# SERIAL_INTERFACES.net
KiCad netlist of a schematic drawn in Altium Designer
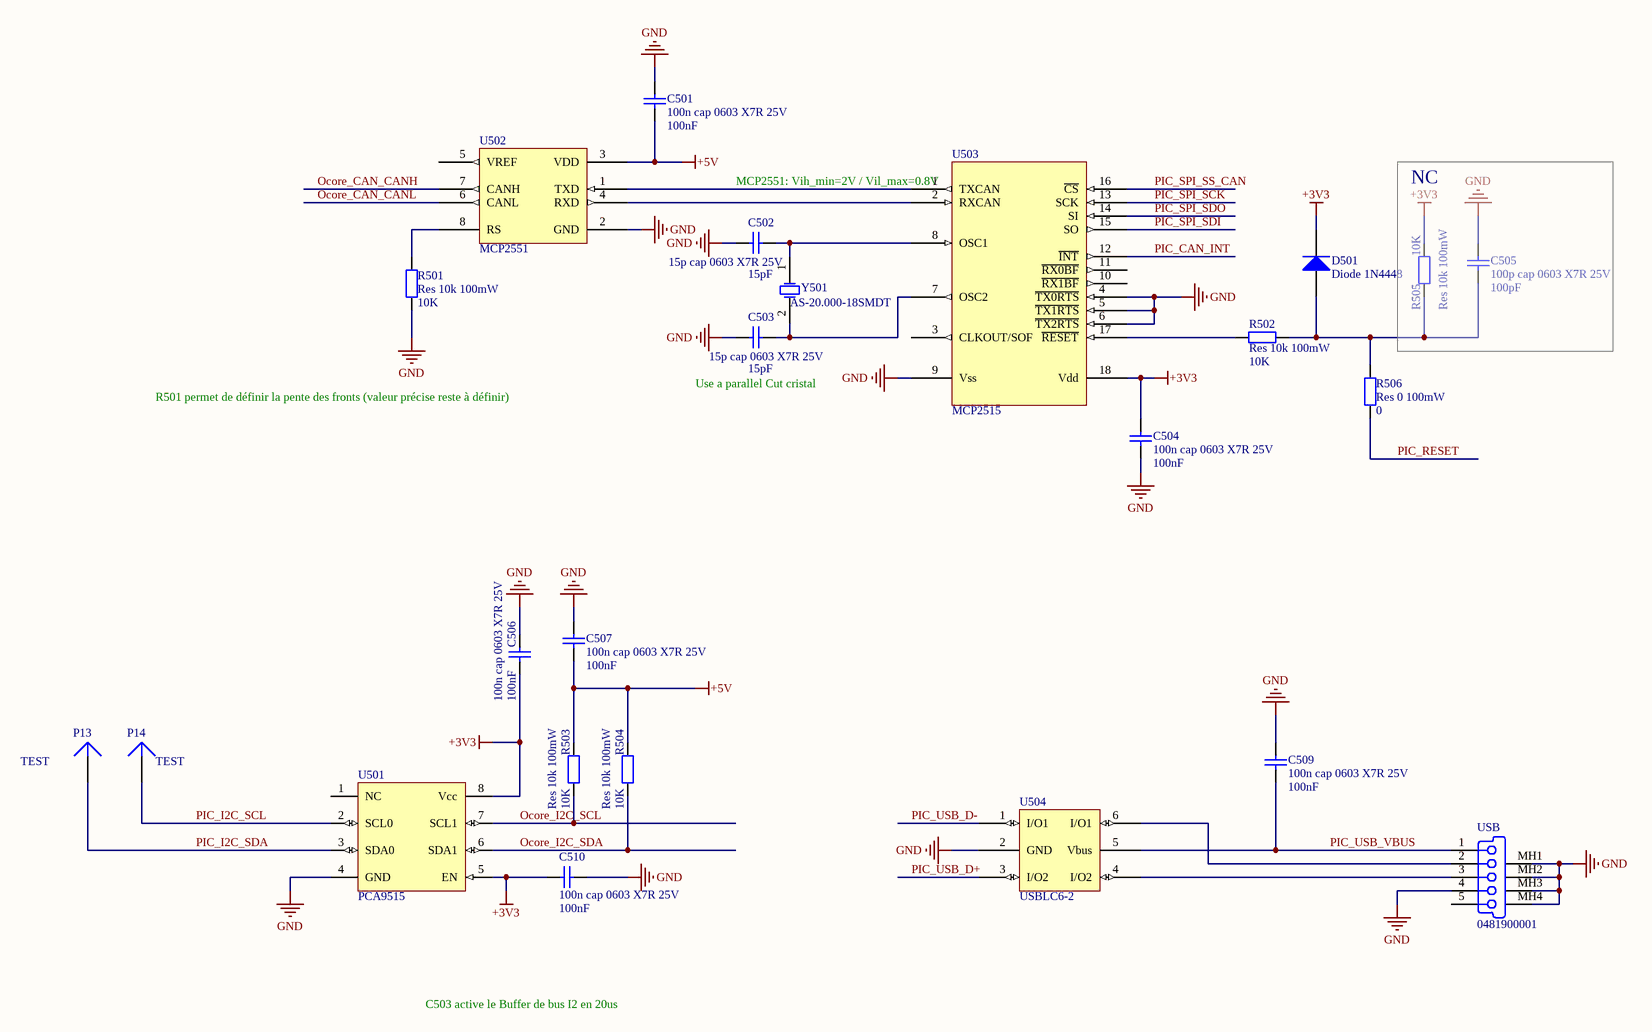
[diagram p0: SERIAL_INTERFACES.SchDoc]

(export (version "E")
  (design (tool "Eeschema 10.0.6"))
  (components
    (comp (ref "C501")
      (value "100n cap 0603 X7R 25V")
      (footprint "1608[0603]")
      (description "Capacitor")
      (fields (field (name "ALTIUM_VALUE") "100nF") (field (name "PUBLISHER") "Altium Limited"))
      (libsource (lib "Miscellaneous Devices") (part "Cap"))
    )
    (comp (ref "C502")
      (value "15p cap 0603 X7R 25V")
      (footprint "1608[0603]")
      (description "Capacitor")
      (fields (field (name "ALTIUM_VALUE") "15pF") (field (name "PUBLISHER") "Altium Limited"))
      (libsource (lib "Miscellaneous Devices") (part "Cap"))
    )
    (comp (ref "C503")
      (value "15p cap 0603 X7R 25V")
      (footprint "1608[0603]")
      (description "Capacitor")
      (fields (field (name "ALTIUM_VALUE") "15pF") (field (name "PUBLISHER") "Altium Limited"))
      (libsource (lib "Miscellaneous Devices") (part "Cap"))
    )
    (comp (ref "C504")
      (value "100n cap 0603 X7R 25V")
      (footprint "1608[0603]")
      (description "Capacitor")
      (fields (field (name "ALTIUM_VALUE") "100nF") (field (name "PUBLISHER") "Altium Limited"))
      (libsource (lib "Miscellaneous Devices") (part "Cap"))
    )
    (comp (ref "C505")
      (value "100p cap 0603 X7R 25V")
      (footprint "1608[0603]")
      (description "Capacitor")
      (fields (field (name "ALTIUM_VALUE") "100pF") (field (name "PUBLISHER") "Altium Limited"))
      (libsource (lib "Miscellaneous Devices") (part "Cap"))
    )
    (comp (ref "C506")
      (value "100n cap 0603 X7R 25V")
      (footprint "1608[0603]")
      (description "Capacitor")
      (fields (field (name "ALTIUM_VALUE") "100nF") (field (name "PUBLISHER") "Altium Limited"))
      (libsource (lib "Miscellaneous Devices") (part "Cap"))
    )
    (comp (ref "C507")
      (value "100n cap 0603 X7R 25V")
      (footprint "1608[0603]")
      (description "Capacitor")
      (fields (field (name "ALTIUM_VALUE") "100nF") (field (name "PUBLISHER") "Altium Limited"))
      (libsource (lib "Miscellaneous Devices") (part "Cap"))
    )
    (comp (ref "C509")
      (value "100n cap 0603 X7R 25V")
      (footprint "1608[0603]")
      (description "Capacitor")
      (fields (field (name "ALTIUM_VALUE") "100nF") (field (name "PUBLISHER") "Altium Limited"))
      (libsource (lib "Miscellaneous Devices") (part "Cap"))
    )
    (comp (ref "C510")
      (value "100n cap 0603 X7R 25V")
      (footprint "1608[0603]")
      (description "Capacitor")
      (fields (field (name "ALTIUM_VALUE") "100nF") (field (name "PUBLISHER") "Altium Limited"))
      (libsource (lib "Miscellaneous Devices") (part "Cap"))
    )
    (comp (ref "D501")
      (value "Diode 1N4448")
      (footprint "1608[0603]")
      (description "High Conductance Fast Diode 0603 case")
      (fields (field (name "PUBLISHER") "Altium Limited"))
      (libsource (lib "Miscellaneous Devices") (part "Diode 1N4448"))
    )
    (comp (ref "P13")
      (value "TEST")
      (footprint "TP1")
      (description "Plug")
      (fields (field (name "PUBLISHER") "Altium Limited"))
      (libsource (lib "Miscellaneous Connectors") (part "Plug"))
    )
    (comp (ref "P14")
      (value "TEST")
      (footprint "TP1")
      (description "Plug")
      (fields (field (name "PUBLISHER") "Altium Limited"))
      (libsource (lib "Miscellaneous Connectors") (part "Plug"))
    )
    (comp (ref "R501")
      (value "Res 10k 100mW")
      (footprint "1608[0603]")
      (description "Resistor")
      (fields (field (name "ALTIUM_VALUE") "10K") (field (name "PUBLISHER") "Altium Limited"))
      (libsource (lib "Miscellaneous Devices") (part "Res2"))
    )
    (comp (ref "R502")
      (value "Res 10k 100mW")
      (footprint "1608[0603]")
      (description "Resistor")
      (fields (field (name "ALTIUM_VALUE") "10K") (field (name "PUBLISHER") "Altium Limited"))
      (libsource (lib "") (part "Res2_1"))
    )
    (comp (ref "R503")
      (value "Res 10k 100mW")
      (footprint "1608[0603]")
      (description "Resistor")
      (fields (field (name "ALTIUM_VALUE") "10K") (field (name "PUBLISHER") "Altium Limited"))
      (libsource (lib "Miscellaneous Devices") (part "Res2"))
    )
    (comp (ref "R504")
      (value "Res 10k 100mW")
      (footprint "1608[0603]")
      (description "Resistor")
      (fields (field (name "ALTIUM_VALUE") "10K") (field (name "PUBLISHER") "Altium Limited"))
      (libsource (lib "Miscellaneous Devices") (part "Res2"))
    )
    (comp (ref "R505")
      (value "Res 10k 100mW")
      (footprint "1608[0603]")
      (description "Resistor")
      (fields (field (name "ALTIUM_VALUE") "10K") (field (name "PUBLISHER") "Altium Limited"))
      (libsource (lib "Miscellaneous Devices") (part "Res2"))
    )
    (comp (ref "R506")
      (value "Res 0 100mW")
      (footprint "1608[0603]")
      (description "Resistor")
      (fields (field (name "ALTIUM_VALUE") "0") (field (name "PUBLISHER") "Altium Limited"))
      (libsource (lib "Miscellaneous Devices") (part "Res2"))
    )
    (comp (ref "U501")
      (value "PCA9515")
      (footprint "751-02_M")
      (description "I2C bus repeater")
      (libsource (lib "pic32USB") (part "PCA9515"))
    )
    (comp (ref "U502")
      (value "MCP2551")
      (footprint "SOIC150-8_N")
      (description "High Speed Can Transceiver")
      (fields (field (name "PUBLISHER") "Altium Limited"))
      (libsource (lib "Microchip Interface Line Transceiver") (part "MCP2551"))
    )
    (comp (ref "U503")
      (value "MCP2515")
      (footprint "SOIC127P1030X265-18N")
      (description "Stand Alone CAN Controller With SPI Interface")
      (libsource (lib "Oufff_Lib") (part "MCP2515"))
    )
    (comp (ref "U504")
      (value "USBLC6-2")
      (footprint "SOT23-6")
      (description "Very low capacitance ESD protection")
      (libsource (lib "Oufff_Lib") (part "USBLC6-2"))
    )
    (comp (ref "USB")
      (value "0481900001")
      (footprint "USB")
      (fields (field (name "PUBLISHER") "Altium Limited"))
      (libsource (lib "Molex Serial Bus Mini USB") (part "0481900001"))
    )
    (comp (ref "Y501")
      (value "AS-20.000-18SMDT")
      (footprint "HC49/S")
      (description "Crystal Oscillator")
      (fields (field (name "PUBLISHER") "Altium Limited"))
      (libsource (lib "Miscellaneous Devices") (part "XTAL"))
    )
  )
  (nets
    (net (code "1") (name "+3V3") (class "Default")
      (node (ref "C504") (pin "1") (pinfunction "1_1") (pintype "passive"))
      (node (ref "C506") (pin "1") (pinfunction "1_1") (pintype "passive"))
      (node (ref "C510") (pin "2") (pinfunction "2_2") (pintype "passive"))
      (node (ref "D501") (pin "2") (pinfunction "K_2") (pintype "passive"))
      (node (ref "R505") (pin "2") (pinfunction "2_2") (pintype "passive"))
      (node (ref "U501") (pin "5") (pinfunction "EN_5") (pintype "input"))
      (node (ref "U501") (pin "8") (pinfunction "Vcc_8") (pintype "power_in"))
      (node (ref "U503") (pin "18") (pinfunction "Vdd_18") (pintype "power_in"))
    )
    (net (code "2") (name "+5V") (class "Default")
      (node (ref "C501") (pin "1") (pinfunction "1_1") (pintype "passive"))
      (node (ref "C507") (pin "2") (pinfunction "2_2") (pintype "passive"))
      (node (ref "R503") (pin "2") (pinfunction "2_2") (pintype "passive"))
      (node (ref "R504") (pin "2") (pinfunction "2_2") (pintype "passive"))
      (node (ref "U502") (pin "3") (pinfunction "VDD_3") (pintype "power_in"))
    )
    (net (code "3") (name "/Ocore_CAN_CANH") (class "Default")
      (node (ref "U502") (pin "7") (pinfunction "CANH_7") (pintype "output"))
    )
    (net (code "4") (name "/Ocore_CAN_CANL") (class "Default")
      (node (ref "U502") (pin "6") (pinfunction "CANL_6") (pintype "output"))
    )
    (net (code "5") (name "/Ocore_I2C_SCL") (class "Default")
      (node (ref "R503") (pin "1") (pinfunction "1_1") (pintype "passive"))
      (node (ref "U501") (pin "7") (pinfunction "SCL1_7") (pintype "bidirectional"))
    )
    (net (code "6") (name "/Ocore_I2C_SDA") (class "Default")
      (node (ref "R504") (pin "1") (pinfunction "1_1") (pintype "passive"))
      (node (ref "U501") (pin "6") (pinfunction "SDA1_6") (pintype "bidirectional"))
    )
    (net (code "7") (name "/PIC_CAN_INT") (class "Default")
      (node (ref "U503") (pin "12") (pinfunction "~{INT}_12") (pintype "output"))
    )
    (net (code "8") (name "/PIC_I2C_SCL") (class "Default")
      (node (ref "P14") (pin "1") (pinfunction "1_1") (pintype "passive"))
      (node (ref "U501") (pin "2") (pinfunction "SCL0_2") (pintype "bidirectional"))
    )
    (net (code "9") (name "/PIC_I2C_SDA") (class "Default")
      (node (ref "P13") (pin "1") (pinfunction "1_1") (pintype "passive"))
      (node (ref "U501") (pin "3") (pinfunction "SDA0_3") (pintype "bidirectional"))
    )
    (net (code "10") (name "/PIC_RESET") (class "Default")
      (node (ref "R506") (pin "1") (pinfunction "1_1") (pintype "passive"))
    )
    (net (code "11") (name "/PIC_SPI_SCK") (class "Default")
      (node (ref "U503") (pin "13") (pinfunction "SCK_13") (pintype "input"))
    )
    (net (code "12") (name "/PIC_SPI_SDI") (class "Default")
      (node (ref "U503") (pin "15") (pinfunction "SO_15") (pintype "output"))
    )
    (net (code "13") (name "/PIC_SPI_SDO") (class "Default")
      (node (ref "U503") (pin "14") (pinfunction "SI_14") (pintype "input"))
    )
    (net (code "14") (name "/PIC_SPI_SS_CAN") (class "Default")
      (node (ref "U503") (pin "16") (pinfunction "~{CS}_16") (pintype "input"))
    )
    (net (code "15") (name "/PIC_USB_D+") (class "Default")
      (node (ref "U504") (pin "3") (pinfunction "I/O2_3") (pintype "bidirectional"))
    )
    (net (code "16") (name "/PIC_USB_D-") (class "Default")
      (node (ref "U504") (pin "1") (pinfunction "I/O1_1") (pintype "bidirectional"))
    )
    (net (code "17") (name "/PIC_USB_VBUS") (class "Default")
      (node (ref "C509") (pin "1") (pinfunction "1_1") (pintype "passive"))
      (node (ref "U504") (pin "5") (pinfunction "Vbus_5") (pintype "power_in"))
      (node (ref "USB") (pin "1") (pinfunction "V_BUS_(5V)_1") (pintype "passive"))
    )
    (net (code "18") (name "GND") (class "Default")
      (node (ref "C501") (pin "2") (pinfunction "2_2") (pintype "passive"))
      (node (ref "C502") (pin "1") (pinfunction "1_1") (pintype "passive"))
      (node (ref "C503") (pin "1") (pinfunction "1_1") (pintype "passive"))
      (node (ref "C504") (pin "2") (pinfunction "2_2") (pintype "passive"))
      (node (ref "C505") (pin "2") (pinfunction "2_2") (pintype "passive"))
      (node (ref "C506") (pin "2") (pinfunction "2_2") (pintype "passive"))
      (node (ref "C507") (pin "1") (pinfunction "1_1") (pintype "passive"))
      (node (ref "C509") (pin "2") (pinfunction "2_2") (pintype "passive"))
      (node (ref "C510") (pin "1") (pinfunction "1_1") (pintype "passive"))
      (node (ref "R501") (pin "1") (pinfunction "1_1") (pintype "passive"))
      (node (ref "U501") (pin "4") (pinfunction "GND_4") (pintype "power_in"))
      (node (ref "U502") (pin "2") (pinfunction "GND_2") (pintype "power_in"))
      (node (ref "U503") (pin "4") (pinfunction "~{TX0RTS}_4") (pintype "input"))
      (node (ref "U503") (pin "5") (pinfunction "~{TX1RTS}_5") (pintype "input"))
      (node (ref "U503") (pin "6") (pinfunction "~{TX2RTS}_6") (pintype "input"))
      (node (ref "U503") (pin "9") (pinfunction "Vss_9") (pintype "power_in"))
      (node (ref "U504") (pin "2") (pinfunction "GND_2") (pintype "power_in"))
      (node (ref "USB") (pin "4") (pinfunction "NC_4") (pintype "passive"))
      (node (ref "USB") (pin "MH1") (pinfunction "Tab_MH1") (pintype "passive"))
      (node (ref "USB") (pin "MH2") (pinfunction "Tab_MH2") (pintype "passive"))
      (node (ref "USB") (pin "MH3") (pinfunction "Tab_MH3") (pintype "passive"))
      (node (ref "USB") (pin "MH4") (pinfunction "Tab_MH4") (pintype "passive"))
    )
    (net (code "19") (name "Net-(D501-A)") (class "Default")
      (node (ref "C505") (pin "1") (pinfunction "1_1") (pintype "passive"))
      (node (ref "D501") (pin "1") (pinfunction "A_1") (pintype "passive"))
      (node (ref "R502") (pin "2") (pinfunction "2_2") (pintype "passive"))
      (node (ref "R505") (pin "1") (pinfunction "1_1") (pintype "passive"))
      (node (ref "R506") (pin "2") (pinfunction "2_2") (pintype "passive"))
    )
    (net (code "20") (name "Net-(U502-RS)") (class "Default")
      (node (ref "R501") (pin "2") (pinfunction "2_2") (pintype "passive"))
      (node (ref "U502") (pin "8") (pinfunction "RS_8") (pintype "passive"))
    )
    (net (code "21") (name "Net-(U502-RXD)") (class "Default")
      (node (ref "U502") (pin "4") (pinfunction "RXD_4") (pintype "output"))
      (node (ref "U503") (pin "2") (pinfunction "RXCAN_2") (pintype "input"))
    )
    (net (code "22") (name "Net-(U502-TXD)") (class "Default")
      (node (ref "U502") (pin "1") (pinfunction "TXD_1") (pintype "input"))
      (node (ref "U503") (pin "1") (pinfunction "TXCAN_1") (pintype "output"))
    )
    (net (code "23") (name "Net-(U503-OSC1)") (class "Default")
      (node (ref "C502") (pin "2") (pinfunction "2_2") (pintype "passive"))
      (node (ref "U503") (pin "8") (pinfunction "OSC1_8") (pintype "input"))
      (node (ref "Y501") (pin "1") (pinfunction "OSC1_1") (pintype "passive"))
    )
    (net (code "24") (name "Net-(U503-OSC2)") (class "Default")
      (node (ref "C503") (pin "2") (pinfunction "2_2") (pintype "passive"))
      (node (ref "U503") (pin "7") (pinfunction "OSC2_7") (pintype "output"))
      (node (ref "Y501") (pin "2") (pinfunction "OSC2_2") (pintype "passive"))
    )
    (net (code "25") (name "Net-(U503-~{RESET})") (class "Default")
      (node (ref "R502") (pin "1") (pinfunction "1_1") (pintype "passive"))
      (node (ref "U503") (pin "17") (pinfunction "~{RESET}_17") (pintype "input"))
    )
    (net (code "26") (name "Net-(USB-D+)") (class "Default")
      (node (ref "U504") (pin "4") (pinfunction "I/O2_4") (pintype "bidirectional"))
      (node (ref "USB") (pin "3") (pinfunction "D+_3") (pintype "passive"))
    )
    (net (code "27") (name "Net-(USB-D-)") (class "Default")
      (node (ref "U504") (pin "6") (pinfunction "I/O1_6") (pintype "bidirectional"))
      (node (ref "USB") (pin "2") (pinfunction "D-_2") (pintype "passive"))
    )
    (net (code "28") (name "unconnected-(U501-NC-Pad1)") (class "Default")
      (node (ref "U501") (pin "1") (pinfunction "NC_1") (pintype "passive"))
    )
    (net (code "29") (name "unconnected-(U502-VREF-Pad5)") (class "Default")
      (node (ref "U502") (pin "5") (pinfunction "VREF_5") (pintype "output"))
    )
    (net (code "30") (name "unconnected-(U503-CLKOUT{slash}SOF-Pad3)") (class "Default")
      (node (ref "U503") (pin "3") (pinfunction "CLKOUT/SOF_3") (pintype "output"))
    )
    (net (code "31") (name "unconnected-(U503-~{RX0BF}-Pad11)") (class "Default")
      (node (ref "U503") (pin "11") (pinfunction "~{RX0BF}_11") (pintype "output"))
    )
    (net (code "32") (name "unconnected-(U503-~{RX1BF}-Pad10)") (class "Default")
      (node (ref "U503") (pin "10") (pinfunction "~{RX1BF}_10") (pintype "output"))
    )
    (net (code "33") (name "unconnected-(USB-GND-Pad5)") (class "Default")
      (node (ref "USB") (pin "5") (pinfunction "GND_5") (pintype "passive"))
    )
  )
)
